# Schematic_Rev1.net
KiCad netlist of a schematic drawn in Altium Designer
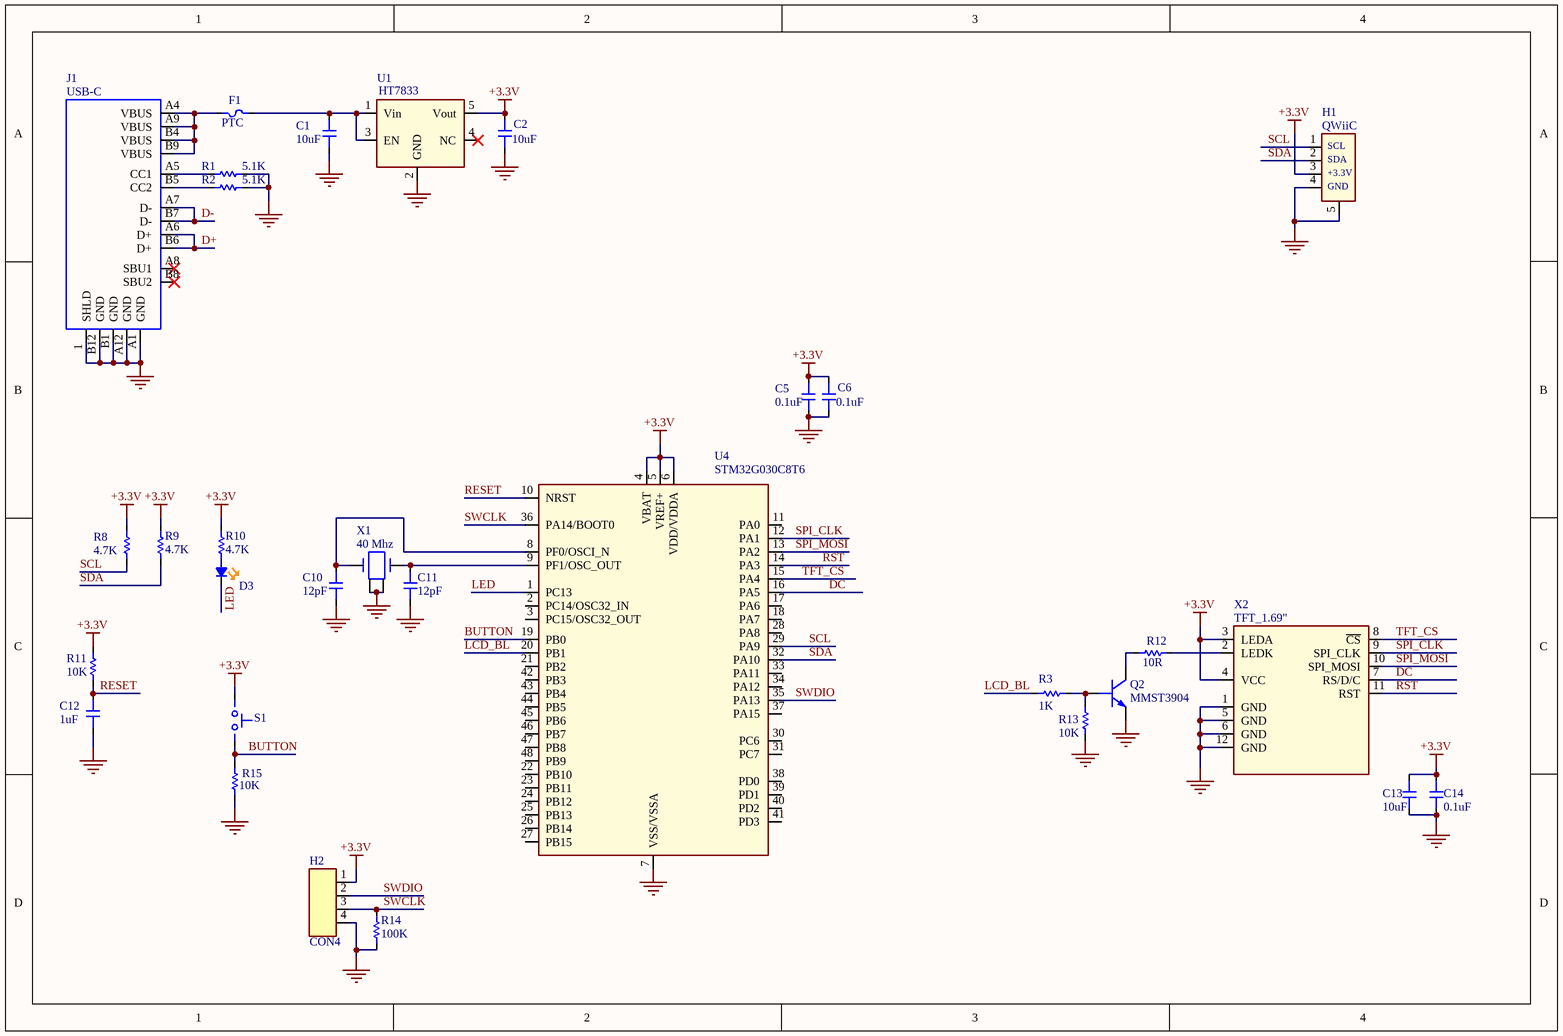
[diagram p0: Schematic_Rev1.SchDoc]

(export (version "E")
  (design (tool "Eeschema 10.0.6"))
  (components
    (comp (ref "C1")
      (value "10uF")
      (footprint "CAPC2012X140N")
      (description "CAP 10uF 0805")
      (libsource (lib "MAR") (part "CAP_0805"))
    )
    (comp (ref "C2")
      (value "10uF")
      (footprint "CAPC2012X140N")
      (description "CAP 10uF 0805")
      (libsource (lib "MAR") (part "CAP_0805"))
    )
    (comp (ref "C5")
      (value "0.1uF")
      (footprint "CAPC1005X56N")
      (description "CAP 0.1uF 0402")
      (libsource (lib "MAR") (part "CAP_0402"))
    )
    (comp (ref "C6")
      (value "0.1uF")
      (footprint "CAPC1005X56N")
      (description "CAP 0.1uF 0402")
      (libsource (lib "MAR") (part "CAP_0402"))
    )
    (comp (ref "C10")
      (value "12pF")
      (footprint "CAPC1005X56N")
      (description "CAP 12pF 0402")
      (libsource (lib "MAR") (part "CAP_0402"))
    )
    (comp (ref "C11")
      (value "12pF")
      (footprint "CAPC1005X56N")
      (description "CAP 12pF 0402")
      (libsource (lib "MAR") (part "CAP_0402"))
    )
    (comp (ref "C12")
      (value "1uF")
      (footprint "CAPC1005X56N")
      (description "CAP 1uF 0402")
      (libsource (lib "MAR") (part "CAP_0402"))
    )
    (comp (ref "C13")
      (value "10uF")
      (footprint "CAPC2012X140N")
      (description "CAP 10uF 0805")
      (libsource (lib "MAR") (part "CAP_0805"))
    )
    (comp (ref "C14")
      (value "0.1uF")
      (footprint "CAPC1608X09L")
      (description "CAP 0.1uF 0603")
      (libsource (lib "MAR") (part "CAP_0603"))
    )
    (comp (ref "D3")
      (value "~")
      (footprint "LED1005X40N-Orange")
      (description "LED Orange 0402")
      (fields (field (name "MANUFACTURER") "Lite-On") (field (name "PART_NUMBER") "C364554"))
      (libsource (lib "MAR") (part "LED_0402_SMALL_Orange"))
    )
    (comp (ref "F1")
      (value "PTC")
      (footprint "RESC1608X06L (0603 FOOTPRINT)")
      (description "PTC FUSE 0.5mA hold, 1A trip 0603")
      (fields (field (name "MANUFACTURER") "JDT Fuse") (field (name "PART_NUMBER") "C2982257"))
      (libsource (lib "MAR") (part "PTC_FUSE_0603"))
    )
    (comp (ref "H1")
      (value "QWiiC")
      (footprint "SM04B-SRSS-TB")
      (description "CONN HEADER 4POS .100 R/A QWIIC")
      (fields (field (name "MANUFACTURER") "JST") (field (name "PART_NUMBER") "PRT-14417"))
      (libsource (lib "MAR") (part "SM04B-SRSS-TB"))
    )
    (comp (ref "H2")
      (value "CON4")
      (footprint "HDR1X4-Empty")
      (description "CONN HEADER 4POS .100\" PADS")
      (fields (field (name "PART_NUMBER") "PADS"))
      (libsource (lib "MAR") (part "CON4"))
    )
    (comp (ref "J1")
      (value "USB-C")
      (footprint "TYPE-C-31-M-12")
      (description "CONN RECPT USB-C")
      (fields (field (name "MANUFACTURER") "KHE") (field (name "PART_NUMBER") "C165948"))
      (libsource (lib "MAR") (part "USB-C"))
    )
    (comp (ref "Q2")
      (value "MMST3904")
      (footprint "SC-70")
      (description "TRANSISTOR NPN GP 40V SC-70")
      (fields (field (name "MANUFACTURER") "Changjiang") (field (name "PART_NUMBER") "C54879"))
      (libsource (lib "MAR") (part "MMST3904"))
    )
    (comp (ref "R1")
      (value "5.1K")
      (footprint "RESC1005X40L (0402 FOOTPRINT)")
      (description "RES 5.1K 0402")
      (libsource (lib "MAR") (part "RES_0402"))
    )
    (comp (ref "R2")
      (value "5.1K")
      (footprint "RESC1005X40L (0402 FOOTPRINT)")
      (description "RES 5.1K 0402")
      (libsource (lib "MAR") (part "RES_0402"))
    )
    (comp (ref "R3")
      (value "1K")
      (footprint "RESC1005X40L (0402 FOOTPRINT)")
      (description "RES 1K 0402")
      (libsource (lib "MAR") (part "RES_0402"))
    )
    (comp (ref "R8")
      (value "4.7K")
      (footprint "RESC1005X40L (0402 FOOTPRINT)")
      (description "RES 4.7K 0402")
      (libsource (lib "MAR") (part "RES_0402"))
    )
    (comp (ref "R9")
      (value "4.7K")
      (footprint "RESC1005X40L (0402 FOOTPRINT)")
      (description "RES 4.7K 0402")
      (libsource (lib "MAR") (part "RES_0402"))
    )
    (comp (ref "R10")
      (value "4.7K")
      (footprint "RESC1005X40L (0402 FOOTPRINT)")
      (description "RES 4.7K 0402")
      (libsource (lib "MAR") (part "RES_0402"))
    )
    (comp (ref "R11")
      (value "10K")
      (footprint "RESC1005X40L (0402 FOOTPRINT)")
      (description "RES 10K 0402")
      (libsource (lib "MAR") (part "RES_0402"))
    )
    (comp (ref "R12")
      (value "10R")
      (footprint "RESC1005X40L (0402 FOOTPRINT)")
      (description "RES 10R 0402")
      (libsource (lib "MAR") (part "RES_0402"))
    )
    (comp (ref "R13")
      (value "10K")
      (footprint "RESC1005X40L (0402 FOOTPRINT)")
      (description "RES 10K 0402")
      (libsource (lib "MAR") (part "RES_0402"))
    )
    (comp (ref "R14")
      (value "100K")
      (footprint "RESC1005X40L (0402 FOOTPRINT)")
      (description "RES 100K 0402")
      (libsource (lib "MAR") (part "RES_0402"))
    )
    (comp (ref "R15")
      (value "10K")
      (footprint "RESC1005X40L (0402 FOOTPRINT)")
      (description "RES 10K 0402")
      (libsource (lib "MAR") (part "RES_0402"))
    )
    (comp (ref "S1")
      (value "~")
      (footprint "TS-1088R-02526")
      (description "Tactile Micro Switch")
      (fields (field (name "PART_NUMBER") "C455281") (field (name "MANUFACTURER") "XUNPU"))
      (libsource (lib "MAR") (part "TS-1088R-02526"))
    )
    (comp (ref "U1")
      (value "HT7833")
      (footprint "SOT95P280X144-5N")
      (description "IC LDO 3.3V 0.5A SOT23-5")
      (fields (field (name "MANUFACTURER") "Holtek") (field (name "PART_NUMBER") "C164106"))
      (libsource (lib "MAR") (part "HT7833"))
    )
    (comp (ref "U4")
      (value "STM32G030C8T6")
      (footprint "LQFP48 0.5MM")
      (description "IC MCU 32BIT 64KB FLASH 48LQFP")
      (fields (field (name "MANUFACTURER") "ST Micro"))
      (libsource (lib "MAR") (part "STM32G030C8T6"))
    )
    (comp (ref "X1")
      (value "40 Mhz")
      (footprint "OSC20X16")
      (description "CRYSTAL 40MHZ 10PF SMD")
      (fields (field (name "PART_NUMBER") "C7294701") (field (name "MANUFACTURER") "Huaxindianzi"))
      (libsource (lib "MAR") (part "40Mhz"))
    )
    (comp (ref "X2")
      (value "TFT_1.69\"")
      (footprint "TFT_GLASS 1.69 INCH SPI")
      (description "1.69 INCH TFT SPI GLASS COLOR ROUNDED CORNERS")
      (fields (field (name "PART_NUMBER") "LH169TIG01"))
      (libsource (lib "MAR") (part "TFT_GLASS 1.69 INCH COLOR SPI"))
    )
  )
  (nets
    (net (code "1") (name "+3.3V") (class "Default")
      (node (ref "C13") (pin "1") (pintype "passive"))
      (node (ref "C14") (pin "1") (pintype "passive"))
      (node (ref "C2") (pin "1") (pintype "passive"))
      (node (ref "C5") (pin "2") (pintype "passive"))
      (node (ref "C6") (pin "2") (pintype "passive"))
      (node (ref "H1") (pin "3") (pintype "passive"))
      (node (ref "H2") (pin "1") (pintype "passive"))
      (node (ref "R10") (pin "1") (pintype "passive"))
      (node (ref "R11") (pin "1") (pintype "passive"))
      (node (ref "R8") (pin "1") (pintype "passive"))
      (node (ref "R9") (pin "1") (pintype "passive"))
      (node (ref "S1") (pin "1") (pinfunction "A_1") (pintype "passive"))
      (node (ref "U1") (pin "5") (pinfunction "Vout_5") (pintype "passive"))
      (node (ref "U4") (pin "4") (pinfunction "VBAT_4") (pintype "power_in"))
      (node (ref "U4") (pin "5") (pinfunction "VREF+_5") (pintype "power_in"))
      (node (ref "U4") (pin "6") (pinfunction "VDD/VDDA_6") (pintype "power_in"))
      (node (ref "X2") (pin "3") (pinfunction "LEDA_3") (pintype "passive"))
      (node (ref "X2") (pin "4") (pinfunction "VCC_4") (pintype "power_in"))
    )
    (net (code "2") (name "/BUTTON") (class "Default")
      (node (ref "R15") (pin "2") (pintype "passive"))
      (node (ref "S1") (pin "2") (pinfunction "B_2") (pintype "passive"))
      (node (ref "U4") (pin "19") (pinfunction "PB0_19") (pintype "passive"))
    )
    (net (code "3") (name "/D+") (class "Default")
      (node (ref "J1") (pin "A6") (pinfunction "D+_A6") (pintype "power_in"))
      (node (ref "J1") (pin "B6") (pinfunction "D+_B6") (pintype "power_in"))
    )
    (net (code "4") (name "/D-") (class "Default")
      (node (ref "J1") (pin "A7") (pinfunction "D-_A7") (pintype "power_in"))
      (node (ref "J1") (pin "B7") (pinfunction "D-_B7") (pintype "power_in"))
    )
    (net (code "5") (name "/DC") (class "Default")
      (node (ref "U4") (pin "16") (pinfunction "PA5_16") (pintype "passive"))
      (node (ref "X2") (pin "7") (pinfunction "RS/D/C_7") (pintype "passive"))
    )
    (net (code "6") (name "/LCD_BL") (class "Default")
      (node (ref "R3") (pin "2") (pintype "passive"))
      (node (ref "U4") (pin "20") (pinfunction "PB1_20") (pintype "passive"))
    )
    (net (code "7") (name "/LED") (class "Default")
      (node (ref "D3") (pin "1") (pintype "passive"))
      (node (ref "U4") (pin "1") (pinfunction "PC13_1") (pintype "passive"))
    )
    (net (code "8") (name "/RESET") (class "Default")
      (node (ref "C12") (pin "2") (pintype "passive"))
      (node (ref "R11") (pin "2") (pintype "passive"))
      (node (ref "U4") (pin "10") (pinfunction "NRST_10") (pintype "passive"))
    )
    (net (code "9") (name "/RST") (class "Default")
      (node (ref "U4") (pin "14") (pinfunction "PA3_14") (pintype "passive"))
      (node (ref "X2") (pin "11") (pinfunction "RST_11") (pintype "passive"))
    )
    (net (code "10") (name "/SCL") (class "Default")
      (node (ref "H1") (pin "1") (pintype "passive"))
      (node (ref "R8") (pin "2") (pintype "passive"))
      (node (ref "U4") (pin "29") (pinfunction "PA9_29") (pintype "passive"))
    )
    (net (code "11") (name "/SDA") (class "Default")
      (node (ref "H1") (pin "2") (pintype "passive"))
      (node (ref "R9") (pin "2") (pintype "passive"))
      (node (ref "U4") (pin "32") (pinfunction "PA10_32") (pintype "passive"))
    )
    (net (code "12") (name "/SPI_CLK") (class "Default")
      (node (ref "U4") (pin "12") (pinfunction "PA1_12") (pintype "passive"))
      (node (ref "X2") (pin "9") (pinfunction "SPI_CLK_9") (pintype "passive"))
    )
    (net (code "13") (name "/SPI_MOSI") (class "Default")
      (node (ref "U4") (pin "13") (pinfunction "PA2_13") (pintype "passive"))
      (node (ref "X2") (pin "10") (pinfunction "SPI_MOSI_10") (pintype "passive"))
    )
    (net (code "14") (name "/SWCLK") (class "Default")
      (node (ref "H2") (pin "3") (pintype "passive"))
      (node (ref "R14") (pin "1") (pintype "passive"))
      (node (ref "U4") (pin "36") (pinfunction "PA14/BOOT0_36") (pintype "passive"))
    )
    (net (code "15") (name "/SWDIO") (class "Default")
      (node (ref "H2") (pin "2") (pintype "passive"))
      (node (ref "U4") (pin "35") (pinfunction "PA13_35") (pintype "passive"))
    )
    (net (code "16") (name "/TFT_CS") (class "Default")
      (node (ref "U4") (pin "15") (pinfunction "PA4_15") (pintype "passive"))
      (node (ref "X2") (pin "8") (pinfunction "~{CS}_8") (pintype "passive"))
    )
    (net (code "17") (name "GND") (class "Default")
      (node (ref "C1") (pin "2") (pintype "passive"))
      (node (ref "C10") (pin "1") (pintype "passive"))
      (node (ref "C11") (pin "1") (pintype "passive"))
      (node (ref "C12") (pin "1") (pintype "passive"))
      (node (ref "C13") (pin "2") (pintype "passive"))
      (node (ref "C14") (pin "2") (pintype "passive"))
      (node (ref "C2") (pin "2") (pintype "passive"))
      (node (ref "C5") (pin "1") (pintype "passive"))
      (node (ref "C6") (pin "1") (pintype "passive"))
      (node (ref "H1") (pin "4") (pintype "passive"))
      (node (ref "H1") (pin "5") (pintype "passive"))
      (node (ref "H2") (pin "4") (pintype "passive"))
      (node (ref "J1") (pin "1") (pinfunction "SHLD_1") (pintype "power_in"))
      (node (ref "J1") (pin "A1") (pinfunction "GND_A1") (pintype "power_in"))
      (node (ref "J1") (pin "A12") (pinfunction "GND_A12") (pintype "power_in"))
      (node (ref "J1") (pin "B1") (pinfunction "GND_B1") (pintype "power_in"))
      (node (ref "J1") (pin "B12") (pinfunction "GND_B12") (pintype "passive"))
      (node (ref "Q2") (pin "2") (pinfunction "E_2") (pintype "passive"))
      (node (ref "R1") (pin "1") (pintype "passive"))
      (node (ref "R13") (pin "2") (pintype "passive"))
      (node (ref "R14") (pin "2") (pintype "passive"))
      (node (ref "R15") (pin "1") (pintype "passive"))
      (node (ref "R2") (pin "1") (pintype "passive"))
      (node (ref "U1") (pin "2") (pinfunction "GND_2") (pintype "power_in"))
      (node (ref "U4") (pin "7") (pinfunction "VSS/VSSA_7") (pintype "power_in"))
      (node (ref "X1") (pin "2") (pinfunction "2_2") (pintype "power_in"))
      (node (ref "X1") (pin "4") (pinfunction "4_4") (pintype "power_in"))
      (node (ref "X2") (pin "1") (pinfunction "GND_1") (pintype "power_in"))
      (node (ref "X2") (pin "12") (pinfunction "GND_12") (pintype "power_in"))
      (node (ref "X2") (pin "5") (pinfunction "GND_5") (pintype "power_in"))
      (node (ref "X2") (pin "6") (pinfunction "GND_6") (pintype "power_in"))
    )
    (net (code "18") (name "Net-(D3-Pad2)") (class "Default")
      (node (ref "D3") (pin "2") (pintype "passive"))
      (node (ref "R10") (pin "2") (pintype "passive"))
    )
    (net (code "19") (name "Net-(F1-Pad2)") (class "Default")
      (node (ref "F1") (pin "2") (pintype "passive"))
      (node (ref "J1") (pin "A4") (pinfunction "VBUS_A4") (pintype "passive"))
      (node (ref "J1") (pin "A9") (pinfunction "VBUS_A9") (pintype "power_in"))
      (node (ref "J1") (pin "B4") (pinfunction "VBUS_B4") (pintype "power_in"))
      (node (ref "J1") (pin "B9") (pinfunction "VBUS_B9") (pintype "passive"))
    )
    (net (code "20") (name "Net-(J1-CC1)") (class "Default")
      (node (ref "J1") (pin "A5") (pinfunction "CC1_A5") (pintype "power_in"))
      (node (ref "R1") (pin "2") (pintype "passive"))
    )
    (net (code "21") (name "Net-(J1-CC2)") (class "Default")
      (node (ref "J1") (pin "B5") (pinfunction "CC2_B5") (pintype "power_in"))
      (node (ref "R2") (pin "2") (pintype "passive"))
    )
    (net (code "22") (name "Net-(Q2-B)") (class "Default")
      (node (ref "Q2") (pin "1") (pinfunction "B_1") (pintype "passive"))
      (node (ref "R13") (pin "1") (pintype "passive"))
      (node (ref "R3") (pin "1") (pintype "passive"))
    )
    (net (code "23") (name "Net-(Q2-C)") (class "Default")
      (node (ref "Q2") (pin "3") (pinfunction "C_3") (pintype "passive"))
      (node (ref "R12") (pin "2") (pintype "passive"))
    )
    (net (code "24") (name "Net-(U1-EN)") (class "Default")
      (node (ref "C1") (pin "1") (pintype "passive"))
      (node (ref "F1") (pin "1") (pintype "passive"))
      (node (ref "U1") (pin "1") (pinfunction "Vin_1") (pintype "passive"))
      (node (ref "U1") (pin "3") (pinfunction "EN_3") (pintype "passive"))
    )
    (net (code "25") (name "Net-(U4-PF0{slash}OSCI_N)") (class "Default")
      (node (ref "C10") (pin "2") (pintype "passive"))
      (node (ref "U4") (pin "8") (pinfunction "PF0/OSCI_N_8") (pintype "passive"))
      (node (ref "X1") (pin "1") (pinfunction "1_1") (pintype "passive"))
    )
    (net (code "26") (name "Net-(U4-PF1{slash}OSC_OUT)") (class "Default")
      (node (ref "C11") (pin "2") (pintype "passive"))
      (node (ref "U4") (pin "9") (pinfunction "PF1/OSC_OUT_9") (pintype "passive"))
      (node (ref "X1") (pin "3") (pinfunction "3_3") (pintype "passive"))
    )
    (net (code "27") (name "Net-(X2-LEDK)") (class "Default")
      (node (ref "R12") (pin "1") (pintype "passive"))
      (node (ref "X2") (pin "2") (pinfunction "LEDK_2") (pintype "passive"))
    )
    (net (code "28") (name "unconnected-(J1-SBU1-PadA8)") (class "Default")
      (node (ref "J1") (pin "A8") (pinfunction "SBU1_A8") (pintype "power_in+no_connect"))
    )
    (net (code "29") (name "unconnected-(J1-SBU2-PadB8)") (class "Default")
      (node (ref "J1") (pin "B8") (pinfunction "SBU2_B8") (pintype "power_in+no_connect"))
    )
    (net (code "30") (name "unconnected-(U1-NC-Pad4)") (class "Default")
      (node (ref "U1") (pin "4") (pinfunction "NC_4") (pintype "passive+no_connect"))
    )
    (net (code "31") (name "unconnected-(U4-PA0-Pad11)") (class "Default")
      (node (ref "U4") (pin "11") (pinfunction "PA0_11") (pintype "passive"))
    )
    (net (code "32") (name "unconnected-(U4-PA6-Pad17)") (class "Default")
      (node (ref "U4") (pin "17") (pinfunction "PA6_17") (pintype "passive"))
    )
    (net (code "33") (name "unconnected-(U4-PA7-Pad18)") (class "Default")
      (node (ref "U4") (pin "18") (pinfunction "PA7_18") (pintype "passive"))
    )
    (net (code "34") (name "unconnected-(U4-PA8-Pad28)") (class "Default")
      (node (ref "U4") (pin "28") (pinfunction "PA8_28") (pintype "passive"))
    )
    (net (code "35") (name "unconnected-(U4-PA11-Pad33)") (class "Default")
      (node (ref "U4") (pin "33") (pinfunction "PA11_33") (pintype "passive"))
    )
    (net (code "36") (name "unconnected-(U4-PA12-Pad34)") (class "Default")
      (node (ref "U4") (pin "34") (pinfunction "PA12_34") (pintype "passive"))
    )
    (net (code "37") (name "unconnected-(U4-PA15-Pad37)") (class "Default")
      (node (ref "U4") (pin "37") (pinfunction "PA15_37") (pintype "passive"))
    )
    (net (code "38") (name "unconnected-(U4-PB2-Pad21)") (class "Default")
      (node (ref "U4") (pin "21") (pinfunction "PB2_21") (pintype "passive"))
    )
    (net (code "39") (name "unconnected-(U4-PB3-Pad42)") (class "Default")
      (node (ref "U4") (pin "42") (pinfunction "PB3_42") (pintype "passive"))
    )
    (net (code "40") (name "unconnected-(U4-PB4-Pad43)") (class "Default")
      (node (ref "U4") (pin "43") (pinfunction "PB4_43") (pintype "passive"))
    )
    (net (code "41") (name "unconnected-(U4-PB5-Pad44)") (class "Default")
      (node (ref "U4") (pin "44") (pinfunction "PB5_44") (pintype "passive"))
    )
    (net (code "42") (name "unconnected-(U4-PB6-Pad45)") (class "Default")
      (node (ref "U4") (pin "45") (pinfunction "PB6_45") (pintype "passive"))
    )
    (net (code "43") (name "unconnected-(U4-PB7-Pad46)") (class "Default")
      (node (ref "U4") (pin "46") (pinfunction "PB7_46") (pintype "passive"))
    )
    (net (code "44") (name "unconnected-(U4-PB8-Pad47)") (class "Default")
      (node (ref "U4") (pin "47") (pinfunction "PB8_47") (pintype "passive"))
    )
    (net (code "45") (name "unconnected-(U4-PB9-Pad48)") (class "Default")
      (node (ref "U4") (pin "48") (pinfunction "PB9_48") (pintype "passive"))
    )
    (net (code "46") (name "unconnected-(U4-PB10-Pad22)") (class "Default")
      (node (ref "U4") (pin "22") (pinfunction "PB10_22") (pintype "passive"))
    )
    (net (code "47") (name "unconnected-(U4-PB11-Pad23)") (class "Default")
      (node (ref "U4") (pin "23") (pinfunction "PB11_23") (pintype "passive"))
    )
    (net (code "48") (name "unconnected-(U4-PB12-Pad24)") (class "Default")
      (node (ref "U4") (pin "24") (pinfunction "PB12_24") (pintype "passive"))
    )
    (net (code "49") (name "unconnected-(U4-PB13-Pad25)") (class "Default")
      (node (ref "U4") (pin "25") (pinfunction "PB13_25") (pintype "passive"))
    )
    (net (code "50") (name "unconnected-(U4-PB14-Pad26)") (class "Default")
      (node (ref "U4") (pin "26") (pinfunction "PB14_26") (pintype "passive"))
    )
    (net (code "51") (name "unconnected-(U4-PB15-Pad27)") (class "Default")
      (node (ref "U4") (pin "27") (pinfunction "PB15_27") (pintype "passive"))
    )
    (net (code "52") (name "unconnected-(U4-PC6-Pad30)") (class "Default")
      (node (ref "U4") (pin "30") (pinfunction "PC6_30") (pintype "passive"))
    )
    (net (code "53") (name "unconnected-(U4-PC7-Pad31)") (class "Default")
      (node (ref "U4") (pin "31") (pinfunction "PC7_31") (pintype "passive"))
    )
    (net (code "54") (name "unconnected-(U4-PC14{slash}OSC32_IN-Pad2)") (class "Default")
      (node (ref "U4") (pin "2") (pinfunction "PC14/OSC32_IN_2") (pintype "passive"))
    )
    (net (code "55") (name "unconnected-(U4-PC15{slash}OSC32_OUT-Pad3)") (class "Default")
      (node (ref "U4") (pin "3") (pinfunction "PC15/OSC32_OUT_3") (pintype "passive"))
    )
    (net (code "56") (name "unconnected-(U4-PD0-Pad38)") (class "Default")
      (node (ref "U4") (pin "38") (pinfunction "PD0_38") (pintype "passive"))
    )
    (net (code "57") (name "unconnected-(U4-PD1-Pad39)") (class "Default")
      (node (ref "U4") (pin "39") (pinfunction "PD1_39") (pintype "passive"))
    )
    (net (code "58") (name "unconnected-(U4-PD2-Pad40)") (class "Default")
      (node (ref "U4") (pin "40") (pinfunction "PD2_40") (pintype "passive"))
    )
    (net (code "59") (name "unconnected-(U4-PD3-Pad41)") (class "Default")
      (node (ref "U4") (pin "41") (pinfunction "PD3_41") (pintype "passive"))
    )
  )
)
